# TankBoardSheet1.net
KiCad netlist of a schematic drawn in Altium Designer
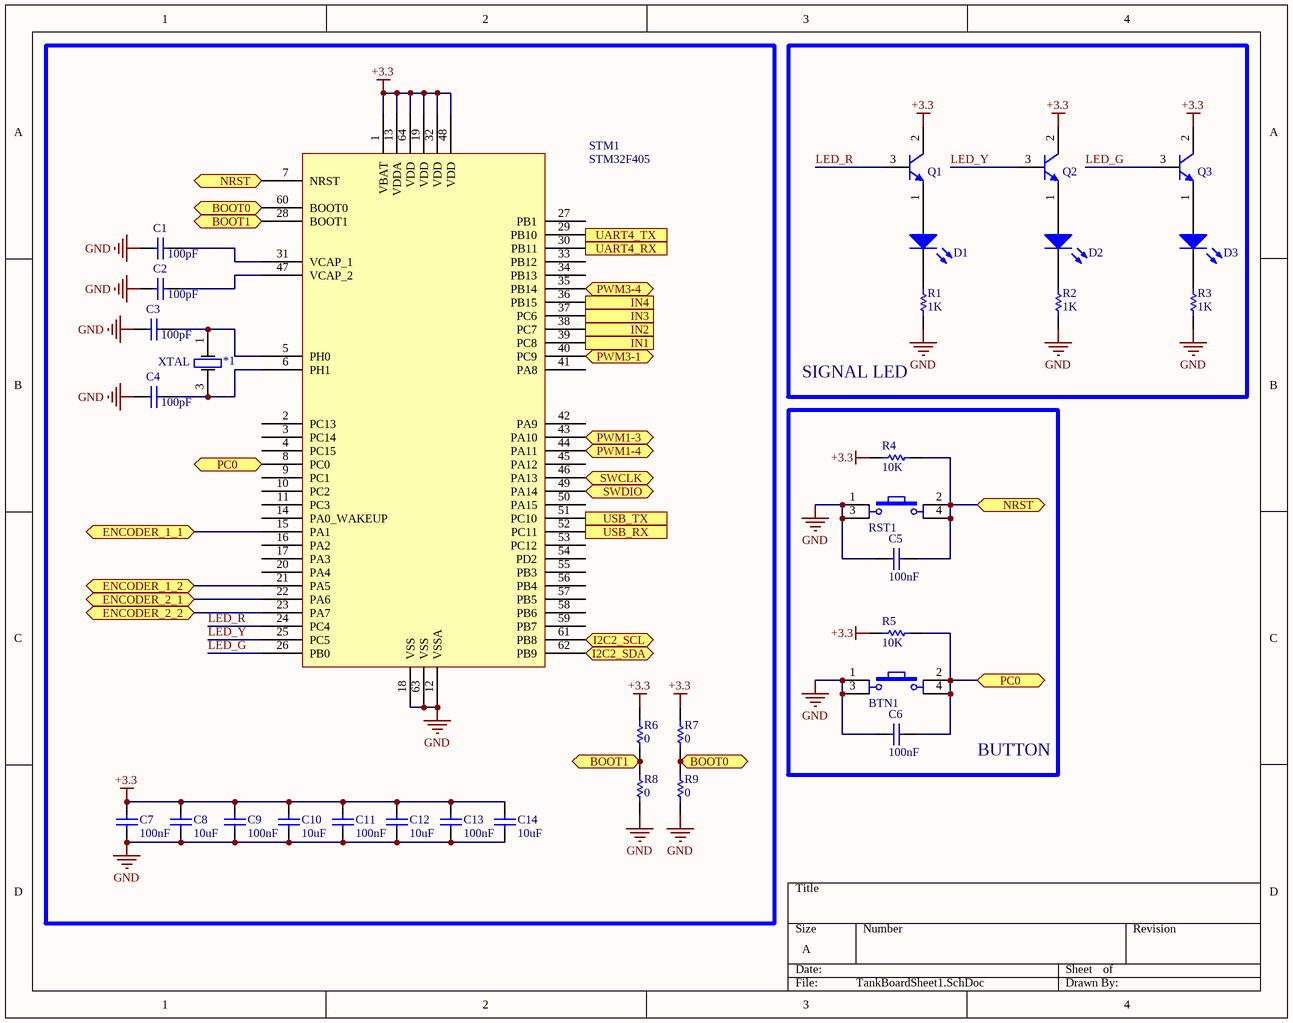
[diagram p0: TankBoardSheet1.SchDoc]

(export (version "E")
  (design (tool "Eeschema 10.0.6"))
  (components
    (comp (ref "*1") (value "XTAL") (footprint "XTAL SMD 4PIN") (libsource (lib "MiclsLib") (part "XTAL")))
    (comp (ref "BTN1")
      (value "SW")
      (footprint "Tact SW 4 pin")
      (description "Switch button 4 pin")
      (libsource (lib "PIF_Library") (part "Tact SW - 4Pin"))
    )
    (comp (ref "C1")
      (value "100pF")
      (footprint "CAP-SM-0603")
      (description "Capacitor")
      (fields (field (name "Comment") "Cap Non-Pol SMD"))
      (libsource (lib "PIF_Library") (part "Cap Non-Pol SMD"))
    )
    (comp (ref "C2")
      (value "100pF")
      (footprint "CAP-SM-0603")
      (description "Capacitor")
      (fields (field (name "Comment") "Cap Non-Pol SMD"))
      (libsource (lib "PIF_Library") (part "Cap Non-Pol SMD"))
    )
    (comp (ref "C3")
      (value "100pF")
      (footprint "CAP-SM-0603")
      (description "Capacitor")
      (fields (field (name "Comment") "Cap Non-Pol SMD"))
      (libsource (lib "PIF_Library") (part "Cap Non-Pol SMD"))
    )
    (comp (ref "C4")
      (value "100pF")
      (footprint "CAP-SM-0603")
      (description "Capacitor")
      (fields (field (name "Comment") "Cap Non-Pol SMD"))
      (libsource (lib "PIF_Library") (part "Cap Non-Pol SMD"))
    )
    (comp (ref "C5")
      (value "100nF")
      (footprint "CAP-SM-0603")
      (description "Capacitor")
      (fields (field (name "Comment") "Cap Non-Pol SMD"))
      (libsource (lib "PIF_Library") (part "Cap Non-Pol SMD"))
    )
    (comp (ref "C6")
      (value "100nF")
      (footprint "CAP-SM-0603")
      (description "Capacitor")
      (fields (field (name "Comment") "Cap Non-Pol SMD"))
      (libsource (lib "PIF_Library") (part "Cap Non-Pol SMD"))
    )
    (comp (ref "C7")
      (value "100nF")
      (footprint "CAP-SM-0603")
      (description "Capacitor")
      (fields (field (name "Comment") "Cap Non-Pol SMD"))
      (libsource (lib "PIF_Library") (part "Cap Non-Pol SMD"))
    )
    (comp (ref "C8")
      (value "10uF")
      (footprint "CAP-SM-0603")
      (description "Capacitor")
      (fields (field (name "Comment") "Cap Non-Pol SMD"))
      (libsource (lib "PIF_Library") (part "Cap Non-Pol SMD"))
    )
    (comp (ref "C9")
      (value "100nF")
      (footprint "CAP-SM-0603")
      (description "Capacitor")
      (fields (field (name "Comment") "Cap Non-Pol SMD"))
      (libsource (lib "PIF_Library") (part "Cap Non-Pol SMD"))
    )
    (comp (ref "C10")
      (value "10uF")
      (footprint "CAP-SM-0603")
      (description "Capacitor")
      (fields (field (name "Comment") "Cap Non-Pol SMD"))
      (libsource (lib "PIF_Library") (part "Cap Non-Pol SMD"))
    )
    (comp (ref "C11")
      (value "100nF")
      (footprint "CAP-SM-0603")
      (description "Capacitor")
      (fields (field (name "Comment") "Cap Non-Pol SMD"))
      (libsource (lib "PIF_Library") (part "Cap Non-Pol SMD"))
    )
    (comp (ref "C12")
      (value "10uF")
      (footprint "CAP-SM-0603")
      (description "Capacitor")
      (fields (field (name "Comment") "Cap Non-Pol SMD"))
      (libsource (lib "PIF_Library") (part "Cap Non-Pol SMD"))
    )
    (comp (ref "C13")
      (value "100nF")
      (footprint "CAP-SM-0603")
      (description "Capacitor")
      (fields (field (name "Comment") "Cap Non-Pol SMD"))
      (libsource (lib "PIF_Library") (part "Cap Non-Pol SMD"))
    )
    (comp (ref "C14")
      (value "10uF")
      (footprint "CAP-SM-0603")
      (description "Capacitor")
      (fields (field (name "Comment") "Cap Non-Pol SMD"))
      (libsource (lib "PIF_Library") (part "Cap Non-Pol SMD"))
    )
    (comp (ref "D1")
      (value "LED SMD")
      (footprint "LED_0603_Blue")
      (description "LED")
      (libsource (lib "PIF_Library") (part "LED SMD"))
    )
    (comp (ref "D2")
      (value "LED SMD")
      (footprint "LED_0603_Blue")
      (description "LED")
      (libsource (lib "PIF_Library") (part "LED SMD"))
    )
    (comp (ref "D3")
      (value "LED SMD")
      (footprint "LED_0603_Blue")
      (description "LED")
      (libsource (lib "PIF_Library") (part "LED SMD"))
    )
    (comp (ref "Q1")
      (value "C1815")
      (footprint "SOT23B")
      (description "NPN Bipolar Transistor")
      (libsource (lib "PIF_Library") (part "C1815"))
    )
    (comp (ref "Q2")
      (value "C1815")
      (footprint "SOT23B")
      (description "NPN Bipolar Transistor")
      (libsource (lib "PIF_Library") (part "C1815"))
    )
    (comp (ref "Q3")
      (value "C1815")
      (footprint "SOT23B")
      (description "NPN Bipolar Transistor")
      (libsource (lib "PIF_Library") (part "C1815"))
    )
    (comp (ref "R1")
      (value "1K")
      (footprint "RES-SM-0603")
      (description "Resistor")
      (fields (field (name "Comment") "RESISTOR SMD"))
      (libsource (lib "PIF_Library") (part "RESISTOR SMD"))
    )
    (comp (ref "R2")
      (value "1K")
      (footprint "RES-SM-0603")
      (description "Resistor")
      (fields (field (name "Comment") "RESISTOR SMD"))
      (libsource (lib "PIF_Library") (part "RESISTOR SMD"))
    )
    (comp (ref "R3")
      (value "1K")
      (footprint "RES-SM-0603")
      (description "Resistor")
      (fields (field (name "Comment") "RESISTOR SMD"))
      (libsource (lib "PIF_Library") (part "RESISTOR SMD"))
    )
    (comp (ref "R4")
      (value "10K")
      (footprint "RES-SM-0603")
      (description "Resistor")
      (fields (field (name "Comment") "RESISTOR SMD"))
      (libsource (lib "PIF_Library") (part "RESISTOR SMD"))
    )
    (comp (ref "R5")
      (value "10K")
      (footprint "RES-SM-0603")
      (description "Resistor")
      (fields (field (name "Comment") "RESISTOR SMD"))
      (libsource (lib "PIF_Library") (part "RESISTOR SMD"))
    )
    (comp (ref "R6")
      (value "0")
      (footprint "RES-SM-0603")
      (description "Resistor")
      (fields (field (name "Comment") "RESISTOR SMD"))
      (libsource (lib "PIF_Library") (part "RESISTOR SMD"))
    )
    (comp (ref "R7")
      (value "0")
      (footprint "RES-SM-0603")
      (description "Resistor")
      (fields (field (name "Comment") "RESISTOR SMD"))
      (libsource (lib "PIF_Library") (part "RESISTOR SMD"))
    )
    (comp (ref "R8")
      (value "0")
      (footprint "RES-SM-0603")
      (description "Resistor")
      (fields (field (name "Comment") "RESISTOR SMD"))
      (libsource (lib "PIF_Library") (part "RESISTOR SMD"))
    )
    (comp (ref "R9")
      (value "0")
      (footprint "RES-SM-0603")
      (description "Resistor")
      (fields (field (name "Comment") "RESISTOR SMD"))
      (libsource (lib "PIF_Library") (part "RESISTOR SMD"))
    )
    (comp (ref "RST1")
      (value "SW")
      (footprint "Tact SW 4 pin")
      (description "Switch button 4 pin")
      (libsource (lib "PIF_Library") (part "Tact SW - 4Pin"))
    )
    (comp (ref "STM1")
      (value "STM32F405")
      (footprint "CQFP50P1150X1150X160-64N")
      (libsource (lib "MiclsLib") (part "STM32F405"))
    )
  )
  (nets
    (net (code "1") (name "+3.3") (class "Default")
      (node (ref "C10") (pin "1") (pinfunction "1_1") (pintype "passive"))
      (node (ref "C11") (pin "1") (pinfunction "1_1") (pintype "passive"))
      (node (ref "C12") (pin "1") (pinfunction "1_1") (pintype "passive"))
      (node (ref "C13") (pin "1") (pinfunction "1_1") (pintype "passive"))
      (node (ref "C14") (pin "1") (pinfunction "1_1") (pintype "passive"))
      (node (ref "C7") (pin "1") (pinfunction "1_1") (pintype "passive"))
      (node (ref "C8") (pin "1") (pinfunction "1_1") (pintype "passive"))
      (node (ref "C9") (pin "1") (pinfunction "1_1") (pintype "passive"))
      (node (ref "Q1") (pin "2") (pinfunction "C_2") (pintype "passive"))
      (node (ref "Q2") (pin "2") (pinfunction "C_2") (pintype "passive"))
      (node (ref "Q3") (pin "2") (pinfunction "C_2") (pintype "passive"))
      (node (ref "R4") (pin "1") (pinfunction "1_1") (pintype "passive"))
      (node (ref "R5") (pin "1") (pinfunction "1_1") (pintype "passive"))
      (node (ref "R6") (pin "2") (pinfunction "2_2") (pintype "passive"))
      (node (ref "R7") (pin "2") (pinfunction "2_2") (pintype "passive"))
      (node (ref "STM1") (pin "1") (pinfunction "VBAT_1") (pintype "passive"))
      (node (ref "STM1") (pin "13") (pinfunction "VDDA_13") (pintype "passive"))
      (node (ref "STM1") (pin "19") (pinfunction "VDD_19") (pintype "passive"))
      (node (ref "STM1") (pin "32") (pinfunction "VDD_32") (pintype "passive"))
      (node (ref "STM1") (pin "48") (pinfunction "VDD_48") (pintype "passive"))
      (node (ref "STM1") (pin "64") (pinfunction "VDD_64") (pintype "passive"))
    )
    (net (code "2") (name "/BOOT0") (class "Default")
      (node (ref "R7") (pin "1") (pinfunction "1_1") (pintype "passive"))
      (node (ref "R9") (pin "2") (pinfunction "2_2") (pintype "passive"))
      (node (ref "STM1") (pin "60") (pinfunction "BOOT0_60") (pintype "passive"))
    )
    (net (code "3") (name "/BOOT1") (class "Default")
      (node (ref "R6") (pin "1") (pinfunction "1_1") (pintype "passive"))
      (node (ref "R8") (pin "2") (pinfunction "2_2") (pintype "passive"))
      (node (ref "STM1") (pin "28") (pinfunction "BOOT1_28") (pintype "passive"))
    )
    (net (code "4") (name "/ENCODER_1_1") (class "Default")
      (node (ref "STM1") (pin "15") (pinfunction "PA1_15") (pintype "passive"))
    )
    (net (code "5") (name "/ENCODER_1_2") (class "Default")
      (node (ref "STM1") (pin "21") (pinfunction "PA5_21") (pintype "passive"))
    )
    (net (code "6") (name "/ENCODER_2_1") (class "Default")
      (node (ref "STM1") (pin "22") (pinfunction "PA6_22") (pintype "passive"))
    )
    (net (code "7") (name "/ENCODER_2_2") (class "Default")
      (node (ref "STM1") (pin "23") (pinfunction "PA7_23") (pintype "passive"))
    )
    (net (code "8") (name "/I2C2_SCL") (class "Default")
      (node (ref "STM1") (pin "61") (pinfunction "PB8_61") (pintype "passive"))
    )
    (net (code "9") (name "/I2C2_SDA") (class "Default")
      (node (ref "STM1") (pin "62") (pinfunction "PB9_62") (pintype "passive"))
    )
    (net (code "10") (name "/IN1") (class "Default")
      (node (ref "STM1") (pin "39") (pinfunction "PC8_39") (pintype "passive"))
    )
    (net (code "11") (name "/IN2") (class "Default")
      (node (ref "STM1") (pin "38") (pinfunction "PC7_38") (pintype "passive"))
    )
    (net (code "12") (name "/IN3") (class "Default")
      (node (ref "STM1") (pin "37") (pinfunction "PC6_37") (pintype "passive"))
    )
    (net (code "13") (name "/IN4") (class "Default")
      (node (ref "STM1") (pin "36") (pinfunction "PB15_36") (pintype "passive"))
    )
    (net (code "14") (name "/LED_G") (class "Default")
      (node (ref "Q3") (pin "3") (pinfunction "B_3") (pintype "passive"))
      (node (ref "STM1") (pin "26") (pinfunction "PB0_26") (pintype "passive"))
    )
    (net (code "15") (name "/LED_R") (class "Default")
      (node (ref "Q1") (pin "3") (pinfunction "B_3") (pintype "passive"))
      (node (ref "STM1") (pin "24") (pinfunction "PC4_24") (pintype "passive"))
    )
    (net (code "16") (name "/LED_Y") (class "Default")
      (node (ref "Q2") (pin "3") (pinfunction "B_3") (pintype "passive"))
      (node (ref "STM1") (pin "25") (pinfunction "PC5_25") (pintype "passive"))
    )
    (net (code "17") (name "/NRST") (class "Default")
      (node (ref "C5") (pin "1") (pinfunction "1_1") (pintype "passive"))
      (node (ref "R4") (pin "2") (pinfunction "2_2") (pintype "passive"))
      (node (ref "RST1") (pin "2") (pintype "passive"))
      (node (ref "RST1") (pin "4") (pintype "passive"))
      (node (ref "STM1") (pin "7") (pinfunction "NRST_7") (pintype "passive"))
    )
    (net (code "18") (name "/PC0") (class "Default")
      (node (ref "BTN1") (pin "2") (pintype "passive"))
      (node (ref "BTN1") (pin "4") (pintype "passive"))
      (node (ref "C6") (pin "1") (pinfunction "1_1") (pintype "passive"))
      (node (ref "R5") (pin "2") (pinfunction "2_2") (pintype "passive"))
      (node (ref "STM1") (pin "8") (pinfunction "PC0_8") (pintype "passive"))
    )
    (net (code "19") (name "/PWM1-3") (class "Default")
      (node (ref "STM1") (pin "43") (pinfunction "PA10_43") (pintype "passive"))
    )
    (net (code "20") (name "/PWM1-4") (class "Default")
      (node (ref "STM1") (pin "44") (pinfunction "PA11_44") (pintype "passive"))
    )
    (net (code "21") (name "/PWM3-1") (class "Default")
      (node (ref "STM1") (pin "40") (pinfunction "PC9_40") (pintype "passive"))
    )
    (net (code "22") (name "/PWM3-4") (class "Default")
      (node (ref "STM1") (pin "35") (pinfunction "PB14_35") (pintype "passive"))
    )
    (net (code "23") (name "/SWCLK") (class "Default")
      (node (ref "STM1") (pin "46") (pinfunction "PA13_46") (pintype "passive"))
    )
    (net (code "24") (name "/SWDIO") (class "Default")
      (node (ref "STM1") (pin "49") (pinfunction "PA14_49") (pintype "passive"))
    )
    (net (code "25") (name "/UART4_RX") (class "Default")
      (node (ref "STM1") (pin "30") (pinfunction "PB11_30") (pintype "passive"))
    )
    (net (code "26") (name "/UART4_TX") (class "Default")
      (node (ref "STM1") (pin "29") (pinfunction "PB10_29") (pintype "passive"))
    )
    (net (code "27") (name "/USB_RX") (class "Default")
      (node (ref "STM1") (pin "52") (pinfunction "PC11_52") (pintype "passive"))
    )
    (net (code "28") (name "/USB_TX") (class "Default")
      (node (ref "STM1") (pin "51") (pinfunction "PC10_51") (pintype "passive"))
    )
    (net (code "29") (name "GND") (class "Default")
      (node (ref "BTN1") (pin "1") (pintype "passive"))
      (node (ref "BTN1") (pin "3") (pintype "passive"))
      (node (ref "C1") (pin "1") (pinfunction "1_1") (pintype "passive"))
      (node (ref "C10") (pin "2") (pinfunction "2_2") (pintype "passive"))
      (node (ref "C11") (pin "2") (pinfunction "2_2") (pintype "passive"))
      (node (ref "C12") (pin "2") (pinfunction "2_2") (pintype "passive"))
      (node (ref "C13") (pin "2") (pinfunction "2_2") (pintype "passive"))
      (node (ref "C14") (pin "2") (pinfunction "2_2") (pintype "passive"))
      (node (ref "C2") (pin "1") (pinfunction "1_1") (pintype "passive"))
      (node (ref "C3") (pin "1") (pinfunction "1_1") (pintype "passive"))
      (node (ref "C4") (pin "1") (pinfunction "1_1") (pintype "passive"))
      (node (ref "C5") (pin "2") (pinfunction "2_2") (pintype "passive"))
      (node (ref "C6") (pin "2") (pinfunction "2_2") (pintype "passive"))
      (node (ref "C7") (pin "2") (pinfunction "2_2") (pintype "passive"))
      (node (ref "C8") (pin "2") (pinfunction "2_2") (pintype "passive"))
      (node (ref "C9") (pin "2") (pinfunction "2_2") (pintype "passive"))
      (node (ref "R1") (pin "1") (pinfunction "1_1") (pintype "passive"))
      (node (ref "R2") (pin "1") (pinfunction "1_1") (pintype "passive"))
      (node (ref "R3") (pin "1") (pinfunction "1_1") (pintype "passive"))
      (node (ref "R8") (pin "1") (pinfunction "1_1") (pintype "passive"))
      (node (ref "R9") (pin "1") (pinfunction "1_1") (pintype "passive"))
      (node (ref "RST1") (pin "1") (pintype "passive"))
      (node (ref "RST1") (pin "3") (pintype "passive"))
      (node (ref "STM1") (pin "12") (pinfunction "VSSA_12") (pintype "passive"))
      (node (ref "STM1") (pin "18") (pinfunction "VSS_18") (pintype "passive"))
      (node (ref "STM1") (pin "63") (pinfunction "VSS_63") (pintype "passive"))
    )
    (net (code "30") (name "Net-(*1-8)") (class "Default")
      (node (ref "*1") (pin "1") (pinfunction "8_1") (pintype "passive"))
      (node (ref "C3") (pin "2") (pinfunction "2_2") (pintype "passive"))
      (node (ref "STM1") (pin "5") (pinfunction "PH0_5") (pintype "passive"))
    )
    (net (code "31") (name "Net-(*1-9)") (class "Default")
      (node (ref "*1") (pin "3") (pinfunction "9_3") (pintype "passive"))
      (node (ref "C4") (pin "2") (pinfunction "2_2") (pintype "passive"))
      (node (ref "STM1") (pin "6") (pinfunction "PH1_6") (pintype "passive"))
    )
    (net (code "32") (name "Net-(D1-A)") (class "Default")
      (node (ref "D1") (pin "1") (pinfunction "A_1") (pintype "passive"))
      (node (ref "Q1") (pin "1") (pinfunction "E_1") (pintype "passive"))
    )
    (net (code "33") (name "Net-(D1-K)") (class "Default")
      (node (ref "D1") (pin "2") (pinfunction "K_2") (pintype "passive"))
      (node (ref "R1") (pin "2") (pinfunction "2_2") (pintype "passive"))
    )
    (net (code "34") (name "Net-(D2-A)") (class "Default")
      (node (ref "D2") (pin "1") (pinfunction "A_1") (pintype "passive"))
      (node (ref "Q2") (pin "1") (pinfunction "E_1") (pintype "passive"))
    )
    (net (code "35") (name "Net-(D2-K)") (class "Default")
      (node (ref "D2") (pin "2") (pinfunction "K_2") (pintype "passive"))
      (node (ref "R2") (pin "2") (pinfunction "2_2") (pintype "passive"))
    )
    (net (code "36") (name "Net-(D3-A)") (class "Default")
      (node (ref "D3") (pin "1") (pinfunction "A_1") (pintype "passive"))
      (node (ref "Q3") (pin "1") (pinfunction "E_1") (pintype "passive"))
    )
    (net (code "37") (name "Net-(D3-K)") (class "Default")
      (node (ref "D3") (pin "2") (pinfunction "K_2") (pintype "passive"))
      (node (ref "R3") (pin "2") (pinfunction "2_2") (pintype "passive"))
    )
    (net (code "38") (name "Net-(STM1-VCAP_1)") (class "Default")
      (node (ref "C1") (pin "2") (pinfunction "2_2") (pintype "passive"))
      (node (ref "STM1") (pin "31") (pinfunction "VCAP_1_31") (pintype "passive"))
    )
    (net (code "39") (name "Net-(STM1-VCAP_2)") (class "Default")
      (node (ref "C2") (pin "2") (pinfunction "2_2") (pintype "passive"))
      (node (ref "STM1") (pin "47") (pinfunction "VCAP_2_47") (pintype "passive"))
    )
    (net (code "40") (name "unconnected-(STM1-PA0_WAKEUP-Pad14)") (class "Default")
      (node (ref "STM1") (pin "14") (pinfunction "PA0_WAKEUP_14") (pintype "passive"))
    )
    (net (code "41") (name "unconnected-(STM1-PA2-Pad16)") (class "Default")
      (node (ref "STM1") (pin "16") (pinfunction "PA2_16") (pintype "passive"))
    )
    (net (code "42") (name "unconnected-(STM1-PA3-Pad17)") (class "Default")
      (node (ref "STM1") (pin "17") (pinfunction "PA3_17") (pintype "passive"))
    )
    (net (code "43") (name "unconnected-(STM1-PA4-Pad20)") (class "Default")
      (node (ref "STM1") (pin "20") (pinfunction "PA4_20") (pintype "passive"))
    )
    (net (code "44") (name "unconnected-(STM1-PA8-Pad41)") (class "Default")
      (node (ref "STM1") (pin "41") (pinfunction "PA8_41") (pintype "passive"))
    )
    (net (code "45") (name "unconnected-(STM1-PA9-Pad42)") (class "Default")
      (node (ref "STM1") (pin "42") (pinfunction "PA9_42") (pintype "passive"))
    )
    (net (code "46") (name "unconnected-(STM1-PA12-Pad45)") (class "Default")
      (node (ref "STM1") (pin "45") (pinfunction "PA12_45") (pintype "passive"))
    )
    (net (code "47") (name "unconnected-(STM1-PA15-Pad50)") (class "Default")
      (node (ref "STM1") (pin "50") (pinfunction "PA15_50") (pintype "passive"))
    )
    (net (code "48") (name "unconnected-(STM1-PB1-Pad27)") (class "Default")
      (node (ref "STM1") (pin "27") (pinfunction "PB1_27") (pintype "passive"))
    )
    (net (code "49") (name "unconnected-(STM1-PB3-Pad55)") (class "Default")
      (node (ref "STM1") (pin "55") (pinfunction "PB3_55") (pintype "passive"))
    )
    (net (code "50") (name "unconnected-(STM1-PB4-Pad56)") (class "Default")
      (node (ref "STM1") (pin "56") (pinfunction "PB4_56") (pintype "passive"))
    )
    (net (code "51") (name "unconnected-(STM1-PB5-Pad57)") (class "Default")
      (node (ref "STM1") (pin "57") (pinfunction "PB5_57") (pintype "passive"))
    )
    (net (code "52") (name "unconnected-(STM1-PB6-Pad58)") (class "Default")
      (node (ref "STM1") (pin "58") (pinfunction "PB6_58") (pintype "passive"))
    )
    (net (code "53") (name "unconnected-(STM1-PB7-Pad59)") (class "Default")
      (node (ref "STM1") (pin "59") (pinfunction "PB7_59") (pintype "passive"))
    )
    (net (code "54") (name "unconnected-(STM1-PB12-Pad33)") (class "Default")
      (node (ref "STM1") (pin "33") (pinfunction "PB12_33") (pintype "passive"))
    )
    (net (code "55") (name "unconnected-(STM1-PB13-Pad34)") (class "Default")
      (node (ref "STM1") (pin "34") (pinfunction "PB13_34") (pintype "passive"))
    )
    (net (code "56") (name "unconnected-(STM1-PC1-Pad9)") (class "Default")
      (node (ref "STM1") (pin "9") (pinfunction "PC1_9") (pintype "passive"))
    )
    (net (code "57") (name "unconnected-(STM1-PC2-Pad10)") (class "Default")
      (node (ref "STM1") (pin "10") (pinfunction "PC2_10") (pintype "passive"))
    )
    (net (code "58") (name "unconnected-(STM1-PC3-Pad11)") (class "Default")
      (node (ref "STM1") (pin "11") (pinfunction "PC3_11") (pintype "passive"))
    )
    (net (code "59") (name "unconnected-(STM1-PC12-Pad53)") (class "Default")
      (node (ref "STM1") (pin "53") (pinfunction "PC12_53") (pintype "passive"))
    )
    (net (code "60") (name "unconnected-(STM1-PC13-Pad2)") (class "Default")
      (node (ref "STM1") (pin "2") (pinfunction "PC13_2") (pintype "passive"))
    )
    (net (code "61") (name "unconnected-(STM1-PC14-Pad3)") (class "Default")
      (node (ref "STM1") (pin "3") (pinfunction "PC14_3") (pintype "passive"))
    )
    (net (code "62") (name "unconnected-(STM1-PC15-Pad4)") (class "Default")
      (node (ref "STM1") (pin "4") (pinfunction "PC15_4") (pintype "passive"))
    )
    (net (code "63") (name "unconnected-(STM1-PD2-Pad54)") (class "Default")
      (node (ref "STM1") (pin "54") (pinfunction "PD2_54") (pintype "passive"))
    )
  )
)
